# sar19-main-board.net
KiCad netlist of a schematic drawn in Altium Designer
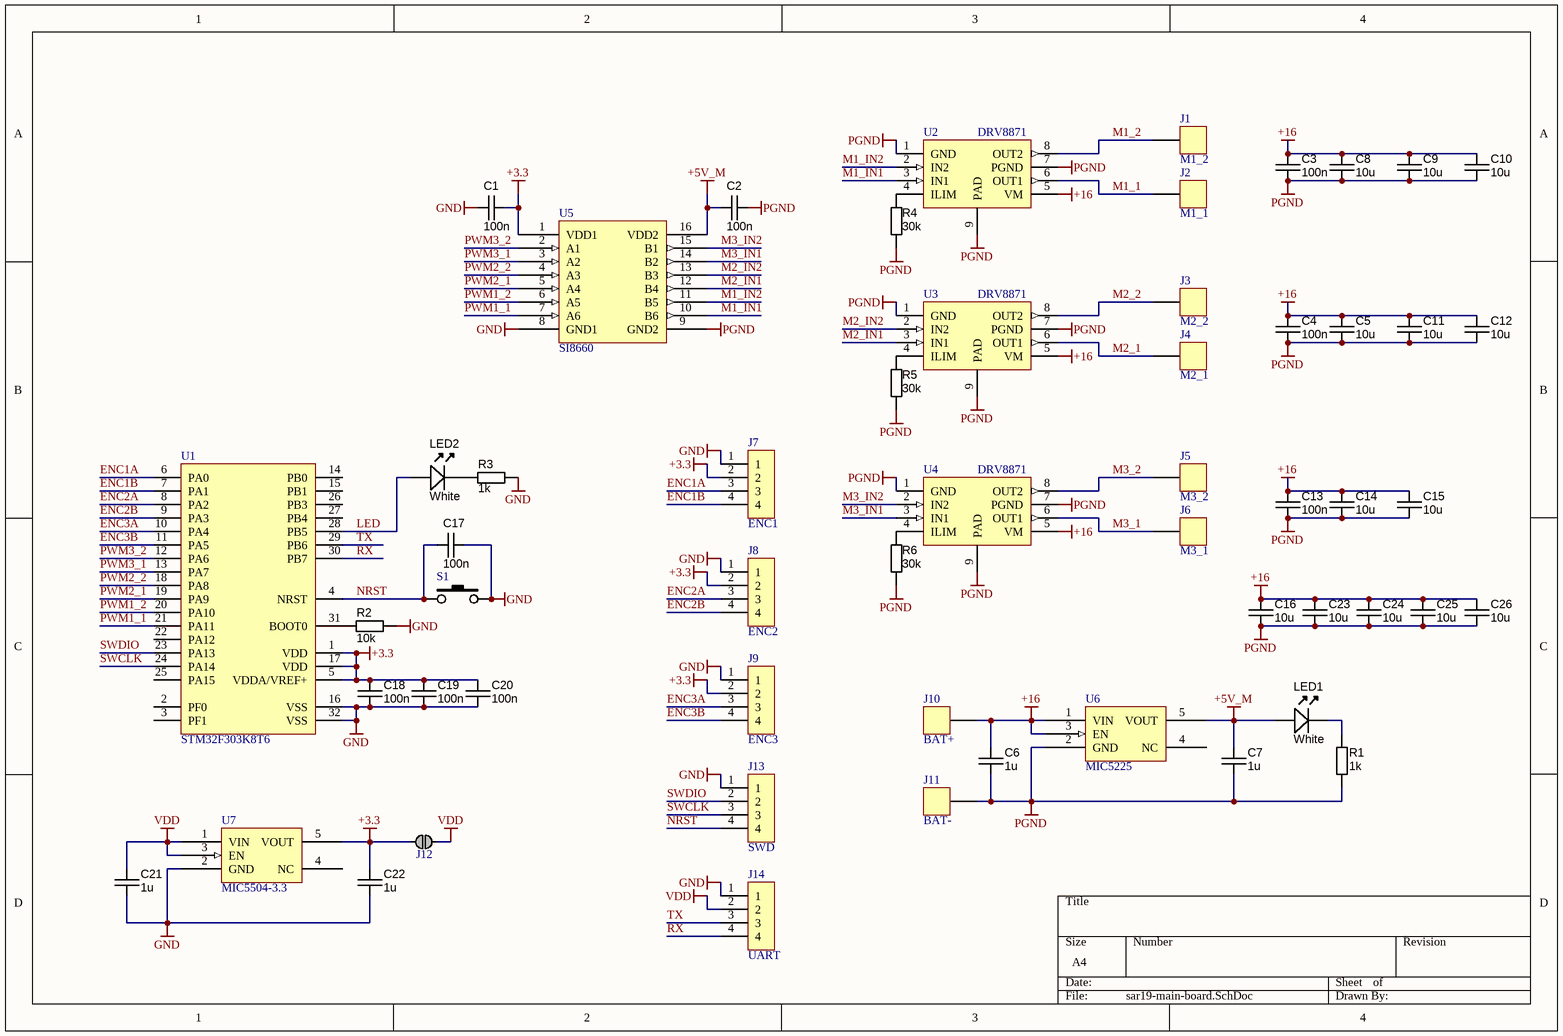
[diagram p0: sar19-main-board.SchDoc]

(export (version "E")
  (design (tool "Eeschema 10.0.6"))
  (components
    (comp (ref "C1")
      (value "100n")
      (footprint "CAPC1608X90N")
      (description "Capacitor SMD Cer 100nF 10% 50V X7R 0603")
      (fields (field (name "TOLERANCE") "±10%") (field (name "Comment") "approved sub OK"))
      (libsource (lib "sar19-main-board") (part "CAPC_100n_0603_X7R_50V_10%"))
    )
    (comp (ref "C2")
      (value "100n")
      (footprint "CAPC1608X90N")
      (description "Capacitor SMD Cer 100nF 10% 50V X7R 0603")
      (fields (field (name "TOLERANCE") "±10%") (field (name "Comment") "approved sub OK"))
      (libsource (lib "sar19-main-board") (part "CAPC_100n_0603_X7R_50V_10%"))
    )
    (comp (ref "C3")
      (value "100n")
      (footprint "CAPC1608X90N")
      (description "Capacitor SMD Cer 100nF 10% 50V X7R 0603")
      (fields (field (name "TOLERANCE") "±10%") (field (name "Comment") "approved sub OK"))
      (libsource (lib "sar19-main-board") (part "CAPC_100n_0603_X7R_50V_10%"))
    )
    (comp (ref "C4")
      (value "100n")
      (footprint "CAPC1608X90N")
      (description "Capacitor SMD Cer 100nF 10% 50V X7R 0603")
      (fields (field (name "TOLERANCE") "±10%") (field (name "Comment") "approved sub OK"))
      (libsource (lib "sar19-main-board") (part "CAPC_100n_0603_X7R_50V_10%"))
    )
    (comp (ref "C5")
      (value "10u")
      (footprint "CAPC3216X180N")
      (description "Capacitor SMD Cer 10uF 10% 16V X7R 1206")
      (fields (field (name "TOLERANCE") "±10%"))
      (libsource (lib "PBL - Capacitors") (part "CAPC_10u_1206_16V"))
    )
    (comp (ref "C6")
      (value "1u")
      (footprint "CAPC1608X90N")
      (description "Capacitor SMD Cer 100nF 10% 50V X7R 0603")
      (fields (field (name "TOLERANCE") "±10%") (field (name "Comment") "approved sub OK"))
      (libsource (lib "sar19-main-board") (part "CAPC_100n_0603_X7R_50V_10%"))
    )
    (comp (ref "C7")
      (value "1u")
      (footprint "CAPC1608X90N")
      (description "Capacitor SMD Cer 100nF 10% 50V X7R 0603")
      (fields (field (name "TOLERANCE") "±10%") (field (name "Comment") "approved sub OK"))
      (libsource (lib "sar19-main-board") (part "CAPC_100n_0603_X7R_50V_10%"))
    )
    (comp (ref "C8")
      (value "10u")
      (footprint "CAPC3216X180N")
      (description "Capacitor SMD Cer 10uF 10% 16V X7R 1206")
      (fields (field (name "TOLERANCE") "±10%"))
      (libsource (lib "PBL - Capacitors") (part "CAPC_10u_1206_16V"))
    )
    (comp (ref "C9")
      (value "10u")
      (footprint "CAPC3216X180N")
      (description "Capacitor SMD Cer 10uF 10% 16V X7R 1206")
      (fields (field (name "TOLERANCE") "±10%"))
      (libsource (lib "PBL - Capacitors") (part "CAPC_10u_1206_16V"))
    )
    (comp (ref "C10")
      (value "10u")
      (footprint "CAPC3216X180N")
      (description "Capacitor SMD Cer 10uF 10% 16V X7R 1206")
      (fields (field (name "TOLERANCE") "±10%"))
      (libsource (lib "PBL - Capacitors") (part "CAPC_10u_1206_16V"))
    )
    (comp (ref "C11")
      (value "10u")
      (footprint "CAPC3216X180N")
      (description "Capacitor SMD Cer 10uF 10% 16V X7R 1206")
      (fields (field (name "TOLERANCE") "±10%"))
      (libsource (lib "PBL - Capacitors") (part "CAPC_10u_1206_16V"))
    )
    (comp (ref "C12")
      (value "10u")
      (footprint "CAPC3216X180N")
      (description "Capacitor SMD Cer 10uF 10% 16V X7R 1206")
      (fields (field (name "TOLERANCE") "±10%"))
      (libsource (lib "PBL - Capacitors") (part "CAPC_10u_1206_16V"))
    )
    (comp (ref "C13")
      (value "100n")
      (footprint "CAPC1608X90N")
      (description "Capacitor SMD Cer 100nF 10% 50V X7R 0603")
      (fields (field (name "TOLERANCE") "±10%") (field (name "Comment") "approved sub OK"))
      (libsource (lib "sar19-main-board") (part "CAPC_100n_0603_X7R_50V_10%"))
    )
    (comp (ref "C14")
      (value "10u")
      (footprint "CAPC3216X180N")
      (description "Capacitor SMD Cer 10uF 10% 16V X7R 1206")
      (fields (field (name "TOLERANCE") "±10%"))
      (libsource (lib "PBL - Capacitors") (part "CAPC_10u_1206_16V"))
    )
    (comp (ref "C15")
      (value "10u")
      (footprint "CAPC3216X180N")
      (description "Capacitor SMD Cer 10uF 10% 16V X7R 1206")
      (fields (field (name "TOLERANCE") "±10%"))
      (libsource (lib "PBL - Capacitors") (part "CAPC_10u_1206_16V"))
    )
    (comp (ref "C16")
      (value "10u")
      (footprint "CAPC3216X180N")
      (description "Capacitor SMD Cer 10uF 10% 16V X7R 1206")
      (fields (field (name "TOLERANCE") "±10%"))
      (libsource (lib "PBL - Capacitors") (part "CAPC_10u_1206_16V"))
    )
    (comp (ref "C17")
      (value "100n")
      (footprint "CAPC1608X90N")
      (description "Capacitor SMD Cer 100nF 10% 50V X7R 0603")
      (fields (field (name "TOLERANCE") "±10%") (field (name "Comment") "approved sub OK"))
      (libsource (lib "sar19-main-board") (part "CAPC_100n_0603_X7R_50V_10%"))
    )
    (comp (ref "C18")
      (value "100n")
      (footprint "CAPC1608X90N")
      (description "Capacitor SMD Cer 100nF 10% 50V X7R 0603")
      (fields (field (name "TOLERANCE") "±10%") (field (name "Comment") "approved sub OK"))
      (libsource (lib "sar19-main-board") (part "CAPC_100n_0603_X7R_50V_10%"))
    )
    (comp (ref "C19")
      (value "100n")
      (footprint "CAPC1608X90N")
      (description "Capacitor SMD Cer 100nF 10% 50V X7R 0603")
      (fields (field (name "TOLERANCE") "±10%") (field (name "Comment") "approved sub OK"))
      (libsource (lib "sar19-main-board") (part "CAPC_100n_0603_X7R_50V_10%"))
    )
    (comp (ref "C20")
      (value "100n")
      (footprint "CAPC1608X90N")
      (description "Capacitor SMD Cer 100nF 10% 50V X7R 0603")
      (fields (field (name "TOLERANCE") "±10%") (field (name "Comment") "approved sub OK"))
      (libsource (lib "sar19-main-board") (part "CAPC_100n_0603_X7R_50V_10%"))
    )
    (comp (ref "C21")
      (value "1u")
      (footprint "CAPC1608X90N")
      (description "Capacitor SMD Cer 100nF 10% 50V X7R 0603")
      (fields (field (name "TOLERANCE") "±10%") (field (name "Comment") "approved sub OK"))
      (libsource (lib "sar19-main-board") (part "CAPC_100n_0603_X7R_50V_10%"))
    )
    (comp (ref "C22")
      (value "1u")
      (footprint "CAPC1608X90N")
      (description "Capacitor SMD Cer 100nF 10% 50V X7R 0603")
      (fields (field (name "TOLERANCE") "±10%") (field (name "Comment") "approved sub OK"))
      (libsource (lib "sar19-main-board") (part "CAPC_100n_0603_X7R_50V_10%"))
    )
    (comp (ref "C23")
      (value "10u")
      (footprint "CAPC3216X180N")
      (description "Capacitor SMD Cer 10uF 10% 16V X7R 1206")
      (fields (field (name "TOLERANCE") "±10%"))
      (libsource (lib "PBL - Capacitors") (part "CAPC_10u_1206_16V"))
    )
    (comp (ref "C24")
      (value "10u")
      (footprint "CAPC3216X180N")
      (description "Capacitor SMD Cer 10uF 10% 16V X7R 1206")
      (fields (field (name "TOLERANCE") "±10%"))
      (libsource (lib "PBL - Capacitors") (part "CAPC_10u_1206_16V"))
    )
    (comp (ref "C25")
      (value "10u")
      (footprint "CAPC3216X180N")
      (description "Capacitor SMD Cer 10uF 10% 16V X7R 1206")
      (fields (field (name "TOLERANCE") "±10%"))
      (libsource (lib "PBL - Capacitors") (part "CAPC_10u_1206_16V"))
    )
    (comp (ref "C26")
      (value "10u")
      (footprint "CAPC3216X180N")
      (description "Capacitor SMD Cer 10uF 10% 16V X7R 1206")
      (fields (field (name "TOLERANCE") "±10%"))
      (libsource (lib "PBL - Capacitors") (part "CAPC_10u_1206_16V"))
    )
    (comp (ref "J1") (value "M1_2") (footprint "POWER-PAD-4x3") (libsource (lib "") (part "HEADER-1_1")))
    (comp (ref "J2") (value "M1_1") (footprint "POWER-PAD-4x3") (libsource (lib "") (part "HEADER-1_1")))
    (comp (ref "J3") (value "M2_2") (footprint "POWER-PAD-4x3") (libsource (lib "") (part "HEADER-1_1")))
    (comp (ref "J4") (value "M2_1") (footprint "POWER-PAD-4x3") (libsource (lib "") (part "HEADER-1_1")))
    (comp (ref "J5") (value "M3_2") (footprint "POWER-PAD-4x3") (libsource (lib "") (part "HEADER-1_1")))
    (comp (ref "J6") (value "M3_1") (footprint "POWER-PAD-4x3") (libsource (lib "") (part "HEADER-1_1")))
    (comp (ref "J7")
      (value "ENC1")
      (footprint "MICRO-MATCH-FOB-04")
      (libsource (lib "connectors_micromatch") (part "HEADER-4"))
    )
    (comp (ref "J8")
      (value "ENC2")
      (footprint "MICRO-MATCH-FOB-04")
      (libsource (lib "connectors_micromatch") (part "HEADER-4"))
    )
    (comp (ref "J9")
      (value "ENC3")
      (footprint "MICRO-MATCH-FOB-04")
      (libsource (lib "connectors_micromatch") (part "HEADER-4"))
    )
    (comp (ref "J10")
      (value "BAT+")
      (footprint "POWER-PAD-4x3")
      (libsource (lib "connectors") (part "HEADER-1"))
    )
    (comp (ref "J11")
      (value "BAT-")
      (footprint "POWER-PAD-4x3")
      (libsource (lib "connectors") (part "HEADER-1"))
    )
    (comp (ref "J12")
      (value "JUMPER")
      (footprint "JUMPER-SMD-1010")
      (libsource (lib "connectors") (part "JUMPER-SMD"))
    )
    (comp (ref "J13")
      (value "SWD")
      (footprint "MICRO-MATCH-FOB-04")
      (libsource (lib "connectors_micromatch") (part "HEADER-4"))
    )
    (comp (ref "J14")
      (value "UART")
      (footprint "MICRO-MATCH-FOB-04")
      (libsource (lib "connectors_micromatch") (part "HEADER-4"))
    )
    (comp (ref "LED1")
      (value "White")
      (footprint "LED-0603-GREEN")
      (description "LED 0603 SMD Green 570nm 50mcd 20mA")
      (libsource (lib "PBL - Light Sources") (part "LED_SMD_Green_0603_570nm"))
    )
    (comp (ref "LED2")
      (value "White")
      (footprint "LED-0603-GREEN")
      (description "LED 0603 SMD Green 570nm 50mcd 20mA")
      (libsource (lib "PBL - Light Sources") (part "LED_SMD_Green_0603_570nm"))
    )
    (comp (ref "R1")
      (value "1k")
      (footprint "RESC1608X55N")
      (description "Resistor SMD chip 1k Ohm 0.1W 1% 0603")
      (fields (field (name "TOLERANCE") "±1%"))
      (libsource (lib "") (part "RES_1K_0603_1%_1"))
    )
    (comp (ref "R2")
      (value "10k")
      (footprint "RESC1608X55N")
      (description "Resistor SMD chip 10k Ohm 0.1W 5% 0603")
      (fields (field (name "TOLERANCE") "±5%"))
      (libsource (lib "PBL - Resistors") (part "RES_10K_0603_5%"))
    )
    (comp (ref "R3")
      (value "1k")
      (footprint "RESC1608X55N")
      (description "Resistor SMD chip 1k Ohm 0.1W 1% 0603")
      (fields (field (name "TOLERANCE") "±1%"))
      (libsource (lib "PBL - Resistors") (part "RES_1K_0603_1%"))
    )
    (comp (ref "R4")
      (value "30k")
      (footprint "RESC1608X55N")
      (description "Resistor SMD chip 1k Ohm 0.1W 1% 0603")
      (fields (field (name "TOLERANCE") "±1%"))
      (libsource (lib "sar19-main-board") (part "RES_1K_0603_1%"))
    )
    (comp (ref "R5")
      (value "30k")
      (footprint "RESC1608X55N")
      (description "Resistor SMD chip 1k Ohm 0.1W 1% 0603")
      (fields (field (name "TOLERANCE") "±1%"))
      (libsource (lib "sar19-main-board") (part "RES_1K_0603_1%"))
    )
    (comp (ref "R6")
      (value "30k")
      (footprint "RESC1608X55N")
      (description "Resistor SMD chip 1k Ohm 0.1W 1% 0603")
      (fields (field (name "TOLERANCE") "±1%"))
      (libsource (lib "sar19-main-board") (part "RES_1K_0603_1%"))
    )
    (comp (ref "S1")
      (value "PUSHBUTTON")
      (footprint "KMR421NGLFS")
      (libsource (lib "switches") (part "PUSHBUTTON"))
    )
    (comp (ref "U1")
      (value "STM32F303K8T6")
      (footprint "LQFP32")
      (libsource (lib "sar19-main-board") (part "STM32F303K8T6"))
    )
    (comp (ref "U2")
      (value "DRV8871")
      (footprint "HSOP8")
      (libsource (lib "texas_instruments") (part "DRV8871"))
    )
    (comp (ref "U3")
      (value "DRV8871")
      (footprint "HSOP8")
      (libsource (lib "texas_instruments") (part "DRV8871"))
    )
    (comp (ref "U4")
      (value "DRV8871")
      (footprint "HSOP8")
      (libsource (lib "texas_instruments") (part "DRV8871"))
    )
    (comp (ref "U5") (value "SI8660") (footprint "QSOP16") (libsource (lib "digital") (part "SI8660")))
    (comp (ref "U6") (value "MIC5225") (footprint "SOT23-5") (libsource (lib "power") (part "LDO-SOT23-5")))
    (comp (ref "U7")
      (value "MIC5504-3.3")
      (footprint "SOT23-5")
      (libsource (lib "power") (part "LDO-SOT23-5"))
    )
  )
  (nets
    (net (code "1") (name "+3.3") (class "Default")
      (node (ref "C1") (pin "1") (pintype "passive"))
      (node (ref "C18") (pin "1") (pintype "passive"))
      (node (ref "C19") (pin "1") (pintype "passive"))
      (node (ref "C20") (pin "1") (pintype "passive"))
      (node (ref "C22") (pin "1") (pintype "passive"))
      (node (ref "J12") (pin "1") (pinfunction "1_1") (pintype "passive"))
      (node (ref "J7") (pin "2") (pinfunction "2_2") (pintype "passive"))
      (node (ref "J8") (pin "2") (pinfunction "2_2") (pintype "passive"))
      (node (ref "J9") (pin "2") (pinfunction "2_2") (pintype "passive"))
      (node (ref "U1") (pin "1") (pinfunction "VDD_1") (pintype "passive"))
      (node (ref "U1") (pin "17") (pinfunction "VDD_17") (pintype "passive"))
      (node (ref "U1") (pin "5") (pinfunction "VDDA/VREF+_5") (pintype "passive"))
      (node (ref "U5") (pin "1") (pinfunction "VDD1_1") (pintype "power_in"))
      (node (ref "U7") (pin "5") (pinfunction "VOUT_5") (pintype "passive"))
    )
    (net (code "2") (name "+5V_M") (class "Default")
      (node (ref "C2") (pin "1") (pintype "passive"))
      (node (ref "C7") (pin "1") (pintype "passive"))
      (node (ref "LED1") (pin "A") (pinfunction "A_A") (pintype "passive"))
      (node (ref "U5") (pin "16") (pinfunction "VDD2_16") (pintype "power_in"))
      (node (ref "U6") (pin "5") (pinfunction "VOUT_5") (pintype "passive"))
    )
    (net (code "3") (name "+16") (class "Default")
      (node (ref "C10") (pin "1") (pintype "passive"))
      (node (ref "C11") (pin "1") (pintype "passive"))
      (node (ref "C12") (pin "1") (pintype "passive"))
      (node (ref "C13") (pin "1") (pintype "passive"))
      (node (ref "C14") (pin "1") (pintype "passive"))
      (node (ref "C15") (pin "1") (pintype "passive"))
      (node (ref "C16") (pin "1") (pintype "passive"))
      (node (ref "C23") (pin "1") (pintype "passive"))
      (node (ref "C24") (pin "1") (pintype "passive"))
      (node (ref "C25") (pin "1") (pintype "passive"))
      (node (ref "C26") (pin "1") (pintype "passive"))
      (node (ref "C3") (pin "1") (pintype "passive"))
      (node (ref "C4") (pin "1") (pintype "passive"))
      (node (ref "C5") (pin "1") (pintype "passive"))
      (node (ref "C6") (pin "1") (pintype "passive"))
      (node (ref "C8") (pin "1") (pintype "passive"))
      (node (ref "C9") (pin "1") (pintype "passive"))
      (node (ref "J10") (pin "1") (pinfunction "1_1") (pintype "passive"))
      (node (ref "U2") (pin "5") (pinfunction "VM_5") (pintype "passive"))
      (node (ref "U3") (pin "5") (pinfunction "VM_5") (pintype "passive"))
      (node (ref "U4") (pin "5") (pinfunction "VM_5") (pintype "passive"))
      (node (ref "U6") (pin "1") (pinfunction "VIN_1") (pintype "power_in"))
      (node (ref "U6") (pin "3") (pinfunction "EN_3") (pintype "input"))
    )
    (net (code "4") (name "/ENC1A") (class "Default")
      (node (ref "J7") (pin "3") (pinfunction "3_3") (pintype "passive"))
      (node (ref "U1") (pin "6") (pinfunction "PA0_6") (pintype "passive"))
    )
    (net (code "5") (name "/ENC1B") (class "Default")
      (node (ref "J7") (pin "4") (pinfunction "4_4") (pintype "passive"))
      (node (ref "U1") (pin "7") (pinfunction "PA1_7") (pintype "passive"))
    )
    (net (code "6") (name "/ENC2A") (class "Default")
      (node (ref "J8") (pin "3") (pinfunction "3_3") (pintype "passive"))
      (node (ref "U1") (pin "8") (pinfunction "PA2_8") (pintype "passive"))
    )
    (net (code "7") (name "/ENC2B") (class "Default")
      (node (ref "J8") (pin "4") (pinfunction "4_4") (pintype "passive"))
      (node (ref "U1") (pin "9") (pinfunction "PA3_9") (pintype "passive"))
    )
    (net (code "8") (name "/ENC3A") (class "Default")
      (node (ref "J9") (pin "3") (pinfunction "3_3") (pintype "passive"))
      (node (ref "U1") (pin "10") (pinfunction "PA4_10") (pintype "passive"))
    )
    (net (code "9") (name "/ENC3B") (class "Default")
      (node (ref "J9") (pin "4") (pinfunction "4_4") (pintype "passive"))
      (node (ref "U1") (pin "11") (pinfunction "PA5_11") (pintype "passive"))
    )
    (net (code "10") (name "/LED") (class "Default")
      (node (ref "LED2") (pin "A") (pinfunction "A_A") (pintype "passive"))
      (node (ref "U1") (pin "28") (pinfunction "PB5_28") (pintype "passive"))
    )
    (net (code "11") (name "/M1_1") (class "Default")
      (node (ref "J2") (pin "1") (pinfunction "1_1") (pintype "passive"))
      (node (ref "U2") (pin "6") (pinfunction "OUT1_6") (pintype "output"))
    )
    (net (code "12") (name "/M1_2") (class "Default")
      (node (ref "J1") (pin "1") (pinfunction "1_1") (pintype "passive"))
      (node (ref "U2") (pin "8") (pinfunction "OUT2_8") (pintype "output"))
    )
    (net (code "13") (name "/M1_IN1") (class "Default")
      (node (ref "U2") (pin "3") (pinfunction "IN1_3") (pintype "input"))
      (node (ref "U5") (pin "10") (pinfunction "B6_10") (pintype "output"))
    )
    (net (code "14") (name "/M1_IN2") (class "Default")
      (node (ref "U2") (pin "2") (pinfunction "IN2_2") (pintype "input"))
      (node (ref "U5") (pin "11") (pinfunction "B5_11") (pintype "output"))
    )
    (net (code "15") (name "/M2_1") (class "Default")
      (node (ref "J4") (pin "1") (pinfunction "1_1") (pintype "passive"))
      (node (ref "U3") (pin "6") (pinfunction "OUT1_6") (pintype "output"))
    )
    (net (code "16") (name "/M2_2") (class "Default")
      (node (ref "J3") (pin "1") (pinfunction "1_1") (pintype "passive"))
      (node (ref "U3") (pin "8") (pinfunction "OUT2_8") (pintype "output"))
    )
    (net (code "17") (name "/M2_IN1") (class "Default")
      (node (ref "U3") (pin "3") (pinfunction "IN1_3") (pintype "input"))
      (node (ref "U5") (pin "12") (pinfunction "B4_12") (pintype "output"))
    )
    (net (code "18") (name "/M2_IN2") (class "Default")
      (node (ref "U3") (pin "2") (pinfunction "IN2_2") (pintype "input"))
      (node (ref "U5") (pin "13") (pinfunction "B3_13") (pintype "output"))
    )
    (net (code "19") (name "/M3_1") (class "Default")
      (node (ref "J6") (pin "1") (pinfunction "1_1") (pintype "passive"))
      (node (ref "U4") (pin "6") (pinfunction "OUT1_6") (pintype "output"))
    )
    (net (code "20") (name "/M3_2") (class "Default")
      (node (ref "J5") (pin "1") (pinfunction "1_1") (pintype "passive"))
      (node (ref "U4") (pin "8") (pinfunction "OUT2_8") (pintype "output"))
    )
    (net (code "21") (name "/M3_IN1") (class "Default")
      (node (ref "U4") (pin "3") (pinfunction "IN1_3") (pintype "input"))
      (node (ref "U5") (pin "14") (pinfunction "B2_14") (pintype "output"))
    )
    (net (code "22") (name "/M3_IN2") (class "Default")
      (node (ref "U4") (pin "2") (pinfunction "IN2_2") (pintype "input"))
      (node (ref "U5") (pin "15") (pinfunction "B1_15") (pintype "output"))
    )
    (net (code "23") (name "/NRST") (class "Default")
      (node (ref "C17") (pin "2") (pintype "passive"))
      (node (ref "J13") (pin "4") (pinfunction "4_4") (pintype "passive"))
      (node (ref "S1") (pin "1") (pintype "passive"))
      (node (ref "U1") (pin "4") (pinfunction "NRST_4") (pintype "passive"))
    )
    (net (code "24") (name "/PWM1_1") (class "Default")
      (node (ref "U1") (pin "21") (pinfunction "PA11_21") (pintype "passive"))
      (node (ref "U5") (pin "7") (pinfunction "A6_7") (pintype "input"))
    )
    (net (code "25") (name "/PWM1_2") (class "Default")
      (node (ref "U1") (pin "20") (pinfunction "PA10_20") (pintype "passive"))
      (node (ref "U5") (pin "6") (pinfunction "A5_6") (pintype "input"))
    )
    (net (code "26") (name "/PWM2_1") (class "Default")
      (node (ref "U1") (pin "19") (pinfunction "PA9_19") (pintype "passive"))
      (node (ref "U5") (pin "5") (pinfunction "A4_5") (pintype "input"))
    )
    (net (code "27") (name "/PWM2_2") (class "Default")
      (node (ref "U1") (pin "18") (pinfunction "PA8_18") (pintype "passive"))
      (node (ref "U5") (pin "4") (pinfunction "A3_4") (pintype "input"))
    )
    (net (code "28") (name "/PWM3_1") (class "Default")
      (node (ref "U1") (pin "13") (pinfunction "PA7_13") (pintype "passive"))
      (node (ref "U5") (pin "3") (pinfunction "A2_3") (pintype "input"))
    )
    (net (code "29") (name "/PWM3_2") (class "Default")
      (node (ref "U1") (pin "12") (pinfunction "PA6_12") (pintype "passive"))
      (node (ref "U5") (pin "2") (pinfunction "A1_2") (pintype "input"))
    )
    (net (code "30") (name "/RX") (class "Default")
      (node (ref "J14") (pin "4") (pinfunction "4_4") (pintype "passive"))
      (node (ref "U1") (pin "30") (pinfunction "PB7_30") (pintype "passive"))
    )
    (net (code "31") (name "/SWCLK") (class "Default")
      (node (ref "J13") (pin "3") (pinfunction "3_3") (pintype "passive"))
      (node (ref "U1") (pin "24") (pinfunction "PA14_24") (pintype "passive"))
    )
    (net (code "32") (name "/SWDIO") (class "Default")
      (node (ref "J13") (pin "2") (pinfunction "2_2") (pintype "passive"))
      (node (ref "U1") (pin "23") (pinfunction "PA13_23") (pintype "passive"))
    )
    (net (code "33") (name "/TX") (class "Default")
      (node (ref "J14") (pin "3") (pinfunction "3_3") (pintype "passive"))
      (node (ref "U1") (pin "29") (pinfunction "PB6_29") (pintype "passive"))
    )
    (net (code "34") (name "GND") (class "Default")
      (node (ref "C1") (pin "2") (pintype "passive"))
      (node (ref "C17") (pin "1") (pintype "passive"))
      (node (ref "C18") (pin "2") (pintype "passive"))
      (node (ref "C19") (pin "2") (pintype "passive"))
      (node (ref "C20") (pin "2") (pintype "passive"))
      (node (ref "C21") (pin "2") (pintype "passive"))
      (node (ref "C22") (pin "2") (pintype "passive"))
      (node (ref "J13") (pin "1") (pinfunction "1_1") (pintype "passive"))
      (node (ref "J14") (pin "1") (pinfunction "1_1") (pintype "passive"))
      (node (ref "J7") (pin "1") (pinfunction "1_1") (pintype "passive"))
      (node (ref "J8") (pin "1") (pinfunction "1_1") (pintype "passive"))
      (node (ref "J9") (pin "1") (pinfunction "1_1") (pintype "passive"))
      (node (ref "R2") (pin "2") (pinfunction "2_2") (pintype "passive"))
      (node (ref "R3") (pin "2") (pinfunction "2_2") (pintype "passive"))
      (node (ref "S1") (pin "2") (pintype "passive"))
      (node (ref "U1") (pin "16") (pinfunction "VSS_16") (pintype "passive"))
      (node (ref "U1") (pin "32") (pinfunction "VSS_32") (pintype "passive"))
      (node (ref "U5") (pin "8") (pinfunction "GND1_8") (pintype "power_in"))
      (node (ref "U7") (pin "2") (pinfunction "GND_2") (pintype "power_in"))
    )
    (net (code "35") (name "Net-(LED1-PadK)") (class "Default")
      (node (ref "LED1") (pin "K") (pinfunction "K_K") (pintype "passive"))
      (node (ref "R1") (pin "1") (pinfunction "1_1") (pintype "passive"))
    )
    (net (code "36") (name "Net-(LED2-PadK)") (class "Default")
      (node (ref "LED2") (pin "K") (pinfunction "K_K") (pintype "passive"))
      (node (ref "R3") (pin "1") (pinfunction "1_1") (pintype "passive"))
    )
    (net (code "37") (name "Net-(U1-BOOT0)") (class "Default")
      (node (ref "R2") (pin "1") (pinfunction "1_1") (pintype "passive"))
      (node (ref "U1") (pin "31") (pinfunction "BOOT0_31") (pintype "passive"))
    )
    (net (code "38") (name "Net-(U2-ILIM)") (class "Default")
      (node (ref "R4") (pin "1") (pinfunction "1_1") (pintype "passive"))
      (node (ref "U2") (pin "4") (pinfunction "ILIM_4") (pintype "passive"))
    )
    (net (code "39") (name "Net-(U3-ILIM)") (class "Default")
      (node (ref "R5") (pin "1") (pinfunction "1_1") (pintype "passive"))
      (node (ref "U3") (pin "4") (pinfunction "ILIM_4") (pintype "passive"))
    )
    (net (code "40") (name "Net-(U4-ILIM)") (class "Default")
      (node (ref "R6") (pin "1") (pinfunction "1_1") (pintype "passive"))
      (node (ref "U4") (pin "4") (pinfunction "ILIM_4") (pintype "passive"))
    )
    (net (code "41") (name "PGND") (class "Default")
      (node (ref "C10") (pin "2") (pintype "passive"))
      (node (ref "C11") (pin "2") (pintype "passive"))
      (node (ref "C12") (pin "2") (pintype "passive"))
      (node (ref "C13") (pin "2") (pintype "passive"))
      (node (ref "C14") (pin "2") (pintype "passive"))
      (node (ref "C15") (pin "2") (pintype "passive"))
      (node (ref "C16") (pin "2") (pintype "passive"))
      (node (ref "C2") (pin "2") (pintype "passive"))
      (node (ref "C23") (pin "2") (pintype "passive"))
      (node (ref "C24") (pin "2") (pintype "passive"))
      (node (ref "C25") (pin "2") (pintype "passive"))
      (node (ref "C26") (pin "2") (pintype "passive"))
      (node (ref "C3") (pin "2") (pintype "passive"))
      (node (ref "C4") (pin "2") (pintype "passive"))
      (node (ref "C5") (pin "2") (pintype "passive"))
      (node (ref "C6") (pin "2") (pintype "passive"))
      (node (ref "C7") (pin "2") (pintype "passive"))
      (node (ref "C8") (pin "2") (pintype "passive"))
      (node (ref "C9") (pin "2") (pintype "passive"))
      (node (ref "J11") (pin "1") (pinfunction "1_1") (pintype "passive"))
      (node (ref "R1") (pin "2") (pinfunction "2_2") (pintype "passive"))
      (node (ref "R4") (pin "2") (pinfunction "2_2") (pintype "passive"))
      (node (ref "R5") (pin "2") (pinfunction "2_2") (pintype "passive"))
      (node (ref "R6") (pin "2") (pinfunction "2_2") (pintype "passive"))
      (node (ref "U2") (pin "1") (pinfunction "GND_1") (pintype "passive"))
      (node (ref "U2") (pin "7") (pinfunction "PGND_7") (pintype "passive"))
      (node (ref "U2") (pin "9") (pinfunction "PAD_9") (pintype "passive"))
      (node (ref "U3") (pin "1") (pinfunction "GND_1") (pintype "passive"))
      (node (ref "U3") (pin "7") (pinfunction "PGND_7") (pintype "passive"))
      (node (ref "U3") (pin "9") (pinfunction "PAD_9") (pintype "passive"))
      (node (ref "U4") (pin "1") (pinfunction "GND_1") (pintype "passive"))
      (node (ref "U4") (pin "7") (pinfunction "PGND_7") (pintype "passive"))
      (node (ref "U4") (pin "9") (pinfunction "PAD_9") (pintype "passive"))
      (node (ref "U5") (pin "9") (pinfunction "GND2_9") (pintype "power_in"))
      (node (ref "U6") (pin "2") (pinfunction "GND_2") (pintype "power_in"))
    )
    (net (code "42") (name "VDD") (class "Default")
      (node (ref "C21") (pin "1") (pintype "passive"))
      (node (ref "J12") (pin "2") (pinfunction "2_2") (pintype "passive"))
      (node (ref "J14") (pin "2") (pinfunction "2_2") (pintype "passive"))
      (node (ref "U7") (pin "1") (pinfunction "VIN_1") (pintype "power_in"))
      (node (ref "U7") (pin "3") (pinfunction "EN_3") (pintype "input"))
    )
    (net (code "43") (name "unconnected-(U1-PA12-Pad22)") (class "Default")
      (node (ref "U1") (pin "22") (pinfunction "PA12_22") (pintype "passive"))
    )
    (net (code "44") (name "unconnected-(U1-PA15-Pad25)") (class "Default")
      (node (ref "U1") (pin "25") (pinfunction "PA15_25") (pintype "passive"))
    )
    (net (code "45") (name "unconnected-(U1-PB0-Pad14)") (class "Default")
      (node (ref "U1") (pin "14") (pinfunction "PB0_14") (pintype "passive"))
    )
    (net (code "46") (name "unconnected-(U1-PB1-Pad15)") (class "Default")
      (node (ref "U1") (pin "15") (pinfunction "PB1_15") (pintype "passive"))
    )
    (net (code "47") (name "unconnected-(U1-PB3-Pad26)") (class "Default")
      (node (ref "U1") (pin "26") (pinfunction "PB3_26") (pintype "passive"))
    )
    (net (code "48") (name "unconnected-(U1-PB4-Pad27)") (class "Default")
      (node (ref "U1") (pin "27") (pinfunction "PB4_27") (pintype "passive"))
    )
    (net (code "49") (name "unconnected-(U1-PF0-Pad2)") (class "Default")
      (node (ref "U1") (pin "2") (pinfunction "PF0_2") (pintype "passive"))
    )
    (net (code "50") (name "unconnected-(U1-PF1-Pad3)") (class "Default")
      (node (ref "U1") (pin "3") (pinfunction "PF1_3") (pintype "passive"))
    )
    (net (code "51") (name "unconnected-(U6-NC-Pad4)") (class "Default")
      (node (ref "U6") (pin "4") (pinfunction "NC_4") (pintype "power_in"))
    )
    (net (code "52") (name "unconnected-(U7-NC-Pad4)") (class "Default")
      (node (ref "U7") (pin "4") (pinfunction "NC_4") (pintype "power_in"))
    )
  )
)
